# alto-ethernet.net
KiCad netlist of a schematic drawn in EAGLE
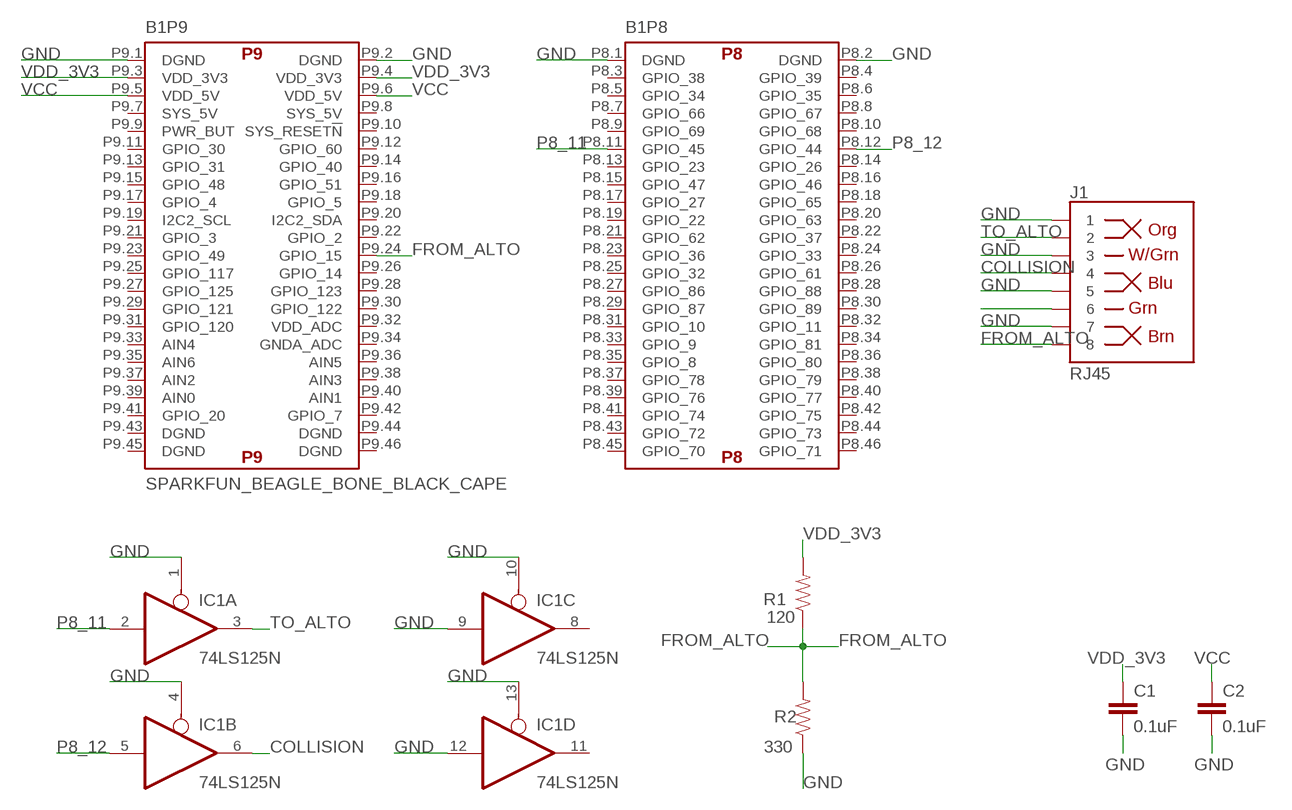
[diagram p0: schematic, sheet 1]

(export (version "E")
  (design (tool "Eeschema 10.0.6"))
  (components
    (comp (ref "B1")
      (value "SPARKFUN_BEAGLE_BONE_BLACK_CAPE")
      (footprint "eagle-import:BEAGLE_BONE_BLACK_CAPE")
      (libsource (lib "eagle-import") (part "SPARKFUN_BEAGLE_BONE_BLACK_CAPE"))
    )
    (comp (ref "C1")
      (value "0.1uF")
      (footprint "eagle-import:CAP-PTH-SMALL-KIT")
      (libsource (lib "eagle-import") (part "0.1UF-KIT-EZ-50V-20%"))
    )
    (comp (ref "C2")
      (value "0.1uF")
      (footprint "eagle-import:CAP-PTH-SMALL-KIT")
      (libsource (lib "eagle-import") (part "0.1UF-KIT-EZ-50V-20%"))
    )
    (comp (ref "IC1")
      (value "74LS125N")
      (footprint "eagle-import:DIL14")
      (libsource (lib "eagle-import") (part "74125NLS"))
    )
    (comp (ref "J1")
      (value "RJ45")
      (footprint "eagle-import:RJ45-8")
      (libsource (lib "eagle-import") (part "RJ45-8"))
    )
    (comp (ref "R1")
      (value "120")
      (footprint "eagle-import:AXIAL-0.3")
      (libsource (lib "eagle-import") (part "RESISTORAXIAL-0.3"))
    )
    (comp (ref "R2")
      (value "330")
      (footprint "eagle-import:AXIAL-0.3")
      (libsource (lib "eagle-import") (part "RESISTORAXIAL-0.3"))
    )
  )
  (nets
    (net (code "1") (name "/COLLISION") (class "Default")
      (node (ref "IC1") (pin "6") (pinfunction "O_6") (pintype "tri_state"))
      (node (ref "J1") (pin "4") (pinfunction "4_4") (pintype "bidirectional"))
    )
    (net (code "2") (name "/FROM_ALTO") (class "Default")
      (node (ref "B1") (pin "P9.24") (pinfunction "GPIO_15_P9.24") (pintype "bidirectional"))
      (node (ref "J1") (pin "8") (pinfunction "8_8") (pintype "bidirectional"))
      (node (ref "R1") (pin "P$1") (pinfunction "1_P$1") (pintype "passive"))
      (node (ref "R2") (pin "P$2") (pinfunction "2_P$2") (pintype "passive"))
    )
    (net (code "3") (name "/GND") (class "Default")
      (node (ref "B1") (pin "P8.1") (pinfunction "DGND_P8.1") (pintype "bidirectional"))
      (node (ref "B1") (pin "P8.2") (pinfunction "DGND_P8.2") (pintype "bidirectional"))
      (node (ref "B1") (pin "P9.1") (pinfunction "DGND_P9.1") (pintype "bidirectional"))
      (node (ref "B1") (pin "P9.2") (pinfunction "DGND_P9.2") (pintype "bidirectional"))
      (node (ref "C1") (pin "2") (pinfunction "2_2") (pintype "passive"))
      (node (ref "C2") (pin "2") (pinfunction "2_2") (pintype "passive"))
      (node (ref "IC1") (pin "1") (pinfunction "OE_1") (pintype "input"))
      (node (ref "IC1") (pin "10") (pinfunction "OE_10") (pintype "input"))
      (node (ref "IC1") (pin "12") (pinfunction "I_12") (pintype "input"))
      (node (ref "IC1") (pin "13") (pinfunction "OE_13") (pintype "input"))
      (node (ref "IC1") (pin "4") (pinfunction "OE_4") (pintype "input"))
      (node (ref "IC1") (pin "9") (pinfunction "I_9") (pintype "input"))
      (node (ref "J1") (pin "1") (pinfunction "1_1") (pintype "bidirectional"))
      (node (ref "J1") (pin "3") (pinfunction "3_3") (pintype "bidirectional"))
      (node (ref "J1") (pin "5") (pinfunction "5_5") (pintype "bidirectional"))
      (node (ref "J1") (pin "7") (pinfunction "7_7") (pintype "bidirectional"))
      (node (ref "R2") (pin "P$1") (pinfunction "1_P$1") (pintype "passive"))
    )
    (net (code "4") (name "/P8_11") (class "Default")
      (node (ref "B1") (pin "P8.11") (pinfunction "GPIO_45_P8.11") (pintype "bidirectional"))
      (node (ref "IC1") (pin "2") (pinfunction "I_2") (pintype "input"))
    )
    (net (code "5") (name "/P8_12") (class "Default")
      (node (ref "B1") (pin "P8.12") (pinfunction "GPIO_44_P8.12") (pintype "bidirectional"))
      (node (ref "IC1") (pin "5") (pinfunction "I_5") (pintype "input"))
    )
    (net (code "6") (name "/TO_ALTO") (class "Default")
      (node (ref "IC1") (pin "3") (pinfunction "O_3") (pintype "tri_state"))
      (node (ref "J1") (pin "2") (pinfunction "2_2") (pintype "bidirectional"))
    )
    (net (code "7") (name "/VCC") (class "Default")
      (node (ref "B1") (pin "P9.5") (pinfunction "VDD_5V_P9.5") (pintype "bidirectional"))
      (node (ref "B1") (pin "P9.6") (pinfunction "VDD_5V_P9.6") (pintype "bidirectional"))
      (node (ref "C2") (pin "1") (pinfunction "1_1") (pintype "passive"))
    )
    (net (code "8") (name "/VDD_3V3") (class "Default")
      (node (ref "B1") (pin "P9.3") (pinfunction "VDD_3V3_P9.3") (pintype "bidirectional"))
      (node (ref "B1") (pin "P9.4") (pinfunction "VDD_3V3_P9.4") (pintype "bidirectional"))
      (node (ref "C1") (pin "1") (pinfunction "1_1") (pintype "passive"))
      (node (ref "R1") (pin "P$2") (pinfunction "2_P$2") (pintype "passive"))
    )
    (net (code "9") (name "unconnected-(B1A-GPIO_8-PadP8.35)") (class "Default")
      (node (ref "B1") (pin "P8.35") (pinfunction "GPIO_8_P8.35") (pintype "bidirectional"))
    )
    (net (code "10") (name "unconnected-(B1A-GPIO_9-PadP8.33)") (class "Default")
      (node (ref "B1") (pin "P8.33") (pinfunction "GPIO_9_P8.33") (pintype "bidirectional"))
    )
    (net (code "11") (name "unconnected-(B1A-GPIO_10-PadP8.31)") (class "Default")
      (node (ref "B1") (pin "P8.31") (pinfunction "GPIO_10_P8.31") (pintype "bidirectional"))
    )
    (net (code "12") (name "unconnected-(B1A-GPIO_11-PadP8.32)") (class "Default")
      (node (ref "B1") (pin "P8.32") (pinfunction "GPIO_11_P8.32") (pintype "bidirectional"))
    )
    (net (code "13") (name "unconnected-(B1A-GPIO_22-PadP8.19)") (class "Default")
      (node (ref "B1") (pin "P8.19") (pinfunction "GPIO_22_P8.19") (pintype "bidirectional"))
    )
    (net (code "14") (name "unconnected-(B1A-GPIO_23-PadP8.13)") (class "Default")
      (node (ref "B1") (pin "P8.13") (pinfunction "GPIO_23_P8.13") (pintype "bidirectional"))
    )
    (net (code "15") (name "unconnected-(B1A-GPIO_26-PadP8.14)") (class "Default")
      (node (ref "B1") (pin "P8.14") (pinfunction "GPIO_26_P8.14") (pintype "bidirectional"))
    )
    (net (code "16") (name "unconnected-(B1A-GPIO_27-PadP8.17)") (class "Default")
      (node (ref "B1") (pin "P8.17") (pinfunction "GPIO_27_P8.17") (pintype "bidirectional"))
    )
    (net (code "17") (name "unconnected-(B1A-GPIO_32-PadP8.25)") (class "Default")
      (node (ref "B1") (pin "P8.25") (pinfunction "GPIO_32_P8.25") (pintype "bidirectional"))
    )
    (net (code "18") (name "unconnected-(B1A-GPIO_33-PadP8.24)") (class "Default")
      (node (ref "B1") (pin "P8.24") (pinfunction "GPIO_33_P8.24") (pintype "bidirectional"))
    )
    (net (code "19") (name "unconnected-(B1A-GPIO_34-PadP8.5)") (class "Default")
      (node (ref "B1") (pin "P8.5") (pinfunction "GPIO_34_P8.5") (pintype "bidirectional"))
    )
    (net (code "20") (name "unconnected-(B1A-GPIO_35-PadP8.6)") (class "Default")
      (node (ref "B1") (pin "P8.6") (pinfunction "GPIO_35_P8.6") (pintype "bidirectional"))
    )
    (net (code "21") (name "unconnected-(B1A-GPIO_36-PadP8.23)") (class "Default")
      (node (ref "B1") (pin "P8.23") (pinfunction "GPIO_36_P8.23") (pintype "bidirectional"))
    )
    (net (code "22") (name "unconnected-(B1A-GPIO_37-PadP8.22)") (class "Default")
      (node (ref "B1") (pin "P8.22") (pinfunction "GPIO_37_P8.22") (pintype "bidirectional"))
    )
    (net (code "23") (name "unconnected-(B1A-GPIO_38-PadP8.3)") (class "Default")
      (node (ref "B1") (pin "P8.3") (pinfunction "GPIO_38_P8.3") (pintype "bidirectional"))
    )
    (net (code "24") (name "unconnected-(B1A-GPIO_39-PadP8.4)") (class "Default")
      (node (ref "B1") (pin "P8.4") (pinfunction "GPIO_39_P8.4") (pintype "bidirectional"))
    )
    (net (code "25") (name "unconnected-(B1A-GPIO_46-PadP8.16)") (class "Default")
      (node (ref "B1") (pin "P8.16") (pinfunction "GPIO_46_P8.16") (pintype "bidirectional"))
    )
    (net (code "26") (name "unconnected-(B1A-GPIO_47-PadP8.15)") (class "Default")
      (node (ref "B1") (pin "P8.15") (pinfunction "GPIO_47_P8.15") (pintype "bidirectional"))
    )
    (net (code "27") (name "unconnected-(B1A-GPIO_61-PadP8.26)") (class "Default")
      (node (ref "B1") (pin "P8.26") (pinfunction "GPIO_61_P8.26") (pintype "bidirectional"))
    )
    (net (code "28") (name "unconnected-(B1A-GPIO_62-PadP8.21)") (class "Default")
      (node (ref "B1") (pin "P8.21") (pinfunction "GPIO_62_P8.21") (pintype "bidirectional"))
    )
    (net (code "29") (name "unconnected-(B1A-GPIO_63-PadP8.20)") (class "Default")
      (node (ref "B1") (pin "P8.20") (pinfunction "GPIO_63_P8.20") (pintype "bidirectional"))
    )
    (net (code "30") (name "unconnected-(B1A-GPIO_65-PadP8.18)") (class "Default")
      (node (ref "B1") (pin "P8.18") (pinfunction "GPIO_65_P8.18") (pintype "bidirectional"))
    )
    (net (code "31") (name "unconnected-(B1A-GPIO_66-PadP8.7)") (class "Default")
      (node (ref "B1") (pin "P8.7") (pinfunction "GPIO_66_P8.7") (pintype "bidirectional"))
    )
    (net (code "32") (name "unconnected-(B1A-GPIO_67-PadP8.8)") (class "Default")
      (node (ref "B1") (pin "P8.8") (pinfunction "GPIO_67_P8.8") (pintype "bidirectional"))
    )
    (net (code "33") (name "unconnected-(B1A-GPIO_68-PadP8.10)") (class "Default")
      (node (ref "B1") (pin "P8.10") (pinfunction "GPIO_68_P8.10") (pintype "bidirectional"))
    )
    (net (code "34") (name "unconnected-(B1A-GPIO_69-PadP8.9)") (class "Default")
      (node (ref "B1") (pin "P8.9") (pinfunction "GPIO_69_P8.9") (pintype "bidirectional"))
    )
    (net (code "35") (name "unconnected-(B1A-GPIO_70-PadP8.45)") (class "Default")
      (node (ref "B1") (pin "P8.45") (pinfunction "GPIO_70_P8.45") (pintype "bidirectional"))
    )
    (net (code "36") (name "unconnected-(B1A-GPIO_71-PadP8.46)") (class "Default")
      (node (ref "B1") (pin "P8.46") (pinfunction "GPIO_71_P8.46") (pintype "bidirectional"))
    )
    (net (code "37") (name "unconnected-(B1A-GPIO_72-PadP8.43)") (class "Default")
      (node (ref "B1") (pin "P8.43") (pinfunction "GPIO_72_P8.43") (pintype "bidirectional"))
    )
    (net (code "38") (name "unconnected-(B1A-GPIO_73-PadP8.44)") (class "Default")
      (node (ref "B1") (pin "P8.44") (pinfunction "GPIO_73_P8.44") (pintype "bidirectional"))
    )
    (net (code "39") (name "unconnected-(B1A-GPIO_74-PadP8.41)") (class "Default")
      (node (ref "B1") (pin "P8.41") (pinfunction "GPIO_74_P8.41") (pintype "bidirectional"))
    )
    (net (code "40") (name "unconnected-(B1A-GPIO_75-PadP8.42)") (class "Default")
      (node (ref "B1") (pin "P8.42") (pinfunction "GPIO_75_P8.42") (pintype "bidirectional"))
    )
    (net (code "41") (name "unconnected-(B1A-GPIO_76-PadP8.39)") (class "Default")
      (node (ref "B1") (pin "P8.39") (pinfunction "GPIO_76_P8.39") (pintype "bidirectional"))
    )
    (net (code "42") (name "unconnected-(B1A-GPIO_77-PadP8.40)") (class "Default")
      (node (ref "B1") (pin "P8.40") (pinfunction "GPIO_77_P8.40") (pintype "bidirectional"))
    )
    (net (code "43") (name "unconnected-(B1A-GPIO_78-PadP8.37)") (class "Default")
      (node (ref "B1") (pin "P8.37") (pinfunction "GPIO_78_P8.37") (pintype "bidirectional"))
    )
    (net (code "44") (name "unconnected-(B1A-GPIO_79-PadP8.38)") (class "Default")
      (node (ref "B1") (pin "P8.38") (pinfunction "GPIO_79_P8.38") (pintype "bidirectional"))
    )
    (net (code "45") (name "unconnected-(B1A-GPIO_80-PadP8.36)") (class "Default")
      (node (ref "B1") (pin "P8.36") (pinfunction "GPIO_80_P8.36") (pintype "bidirectional"))
    )
    (net (code "46") (name "unconnected-(B1A-GPIO_81-PadP8.34)") (class "Default")
      (node (ref "B1") (pin "P8.34") (pinfunction "GPIO_81_P8.34") (pintype "bidirectional"))
    )
    (net (code "47") (name "unconnected-(B1A-GPIO_86-PadP8.27)") (class "Default")
      (node (ref "B1") (pin "P8.27") (pinfunction "GPIO_86_P8.27") (pintype "bidirectional"))
    )
    (net (code "48") (name "unconnected-(B1A-GPIO_87-PadP8.29)") (class "Default")
      (node (ref "B1") (pin "P8.29") (pinfunction "GPIO_87_P8.29") (pintype "bidirectional"))
    )
    (net (code "49") (name "unconnected-(B1A-GPIO_88-PadP8.28)") (class "Default")
      (node (ref "B1") (pin "P8.28") (pinfunction "GPIO_88_P8.28") (pintype "bidirectional"))
    )
    (net (code "50") (name "unconnected-(B1A-GPIO_89-PadP8.30)") (class "Default")
      (node (ref "B1") (pin "P8.30") (pinfunction "GPIO_89_P8.30") (pintype "bidirectional"))
    )
    (net (code "51") (name "unconnected-(B1B-AIN0-PadP9.39)") (class "Default")
      (node (ref "B1") (pin "P9.39") (pinfunction "AIN0_P9.39") (pintype "bidirectional"))
    )
    (net (code "52") (name "unconnected-(B1B-AIN1-PadP9.40)") (class "Default")
      (node (ref "B1") (pin "P9.40") (pinfunction "AIN1_P9.40") (pintype "bidirectional"))
    )
    (net (code "53") (name "unconnected-(B1B-AIN2-PadP9.37)") (class "Default")
      (node (ref "B1") (pin "P9.37") (pinfunction "AIN2_P9.37") (pintype "bidirectional"))
    )
    (net (code "54") (name "unconnected-(B1B-AIN3-PadP9.38)") (class "Default")
      (node (ref "B1") (pin "P9.38") (pinfunction "AIN3_P9.38") (pintype "bidirectional"))
    )
    (net (code "55") (name "unconnected-(B1B-AIN4-PadP9.33)") (class "Default")
      (node (ref "B1") (pin "P9.33") (pinfunction "AIN4_P9.33") (pintype "bidirectional"))
    )
    (net (code "56") (name "unconnected-(B1B-AIN5-PadP9.36)") (class "Default")
      (node (ref "B1") (pin "P9.36") (pinfunction "AIN5_P9.36") (pintype "bidirectional"))
    )
    (net (code "57") (name "unconnected-(B1B-AIN6-PadP9.35)") (class "Default")
      (node (ref "B1") (pin "P9.35") (pinfunction "AIN6_P9.35") (pintype "bidirectional"))
    )
    (net (code "58") (name "unconnected-(B1B-DGND-PadP9.43)") (class "Default")
      (node (ref "B1") (pin "P9.43") (pinfunction "DGND_P9.43") (pintype "bidirectional"))
    )
    (net (code "59") (name "unconnected-(B1B-DGND-PadP9.44)") (class "Default")
      (node (ref "B1") (pin "P9.44") (pinfunction "DGND_P9.44") (pintype "bidirectional"))
    )
    (net (code "60") (name "unconnected-(B1B-DGND-PadP9.45)") (class "Default")
      (node (ref "B1") (pin "P9.45") (pinfunction "DGND_P9.45") (pintype "bidirectional"))
    )
    (net (code "61") (name "unconnected-(B1B-DGND-PadP9.46)") (class "Default")
      (node (ref "B1") (pin "P9.46") (pinfunction "DGND_P9.46") (pintype "bidirectional"))
    )
    (net (code "62") (name "unconnected-(B1B-GNDA_ADC-PadP9.34)") (class "Default")
      (node (ref "B1") (pin "P9.34") (pinfunction "GNDA_ADC_P9.34") (pintype "bidirectional"))
    )
    (net (code "63") (name "unconnected-(B1B-GPIO_2-PadP9.22)") (class "Default")
      (node (ref "B1") (pin "P9.22") (pinfunction "GPIO_2_P9.22") (pintype "bidirectional"))
    )
    (net (code "64") (name "unconnected-(B1B-GPIO_3-PadP9.21)") (class "Default")
      (node (ref "B1") (pin "P9.21") (pinfunction "GPIO_3_P9.21") (pintype "bidirectional"))
    )
    (net (code "65") (name "unconnected-(B1B-GPIO_4-PadP9.17)") (class "Default")
      (node (ref "B1") (pin "P9.17") (pinfunction "GPIO_4_P9.17") (pintype "bidirectional"))
    )
    (net (code "66") (name "unconnected-(B1B-GPIO_5-PadP9.18)") (class "Default")
      (node (ref "B1") (pin "P9.18") (pinfunction "GPIO_5_P9.18") (pintype "bidirectional"))
    )
    (net (code "67") (name "unconnected-(B1B-GPIO_7-PadP9.42)") (class "Default")
      (node (ref "B1") (pin "P9.42") (pinfunction "GPIO_7_P9.42") (pintype "bidirectional"))
    )
    (net (code "68") (name "unconnected-(B1B-GPIO_14-PadP9.26)") (class "Default")
      (node (ref "B1") (pin "P9.26") (pinfunction "GPIO_14_P9.26") (pintype "bidirectional"))
    )
    (net (code "69") (name "unconnected-(B1B-GPIO_20-PadP9.41)") (class "Default")
      (node (ref "B1") (pin "P9.41") (pinfunction "GPIO_20_P9.41") (pintype "bidirectional"))
    )
    (net (code "70") (name "unconnected-(B1B-GPIO_30-PadP9.11)") (class "Default")
      (node (ref "B1") (pin "P9.11") (pinfunction "GPIO_30_P9.11") (pintype "bidirectional"))
    )
    (net (code "71") (name "unconnected-(B1B-GPIO_31-PadP9.13)") (class "Default")
      (node (ref "B1") (pin "P9.13") (pinfunction "GPIO_31_P9.13") (pintype "bidirectional"))
    )
    (net (code "72") (name "unconnected-(B1B-GPIO_40-PadP9.14)") (class "Default")
      (node (ref "B1") (pin "P9.14") (pinfunction "GPIO_40_P9.14") (pintype "bidirectional"))
    )
    (net (code "73") (name "unconnected-(B1B-GPIO_48-PadP9.15)") (class "Default")
      (node (ref "B1") (pin "P9.15") (pinfunction "GPIO_48_P9.15") (pintype "bidirectional"))
    )
    (net (code "74") (name "unconnected-(B1B-GPIO_49-PadP9.23)") (class "Default")
      (node (ref "B1") (pin "P9.23") (pinfunction "GPIO_49_P9.23") (pintype "bidirectional"))
    )
    (net (code "75") (name "unconnected-(B1B-GPIO_51-PadP9.16)") (class "Default")
      (node (ref "B1") (pin "P9.16") (pinfunction "GPIO_51_P9.16") (pintype "bidirectional"))
    )
    (net (code "76") (name "unconnected-(B1B-GPIO_60-PadP9.12)") (class "Default")
      (node (ref "B1") (pin "P9.12") (pinfunction "GPIO_60_P9.12") (pintype "bidirectional"))
    )
    (net (code "77") (name "unconnected-(B1B-GPIO_117-PadP9.25)") (class "Default")
      (node (ref "B1") (pin "P9.25") (pinfunction "GPIO_117_P9.25") (pintype "bidirectional"))
    )
    (net (code "78") (name "unconnected-(B1B-GPIO_120-PadP9.31)") (class "Default")
      (node (ref "B1") (pin "P9.31") (pinfunction "GPIO_120_P9.31") (pintype "bidirectional"))
    )
    (net (code "79") (name "unconnected-(B1B-GPIO_121-PadP9.29)") (class "Default")
      (node (ref "B1") (pin "P9.29") (pinfunction "GPIO_121_P9.29") (pintype "bidirectional"))
    )
    (net (code "80") (name "unconnected-(B1B-GPIO_122-PadP9.30)") (class "Default")
      (node (ref "B1") (pin "P9.30") (pinfunction "GPIO_122_P9.30") (pintype "bidirectional"))
    )
    (net (code "81") (name "unconnected-(B1B-GPIO_123-PadP9.28)") (class "Default")
      (node (ref "B1") (pin "P9.28") (pinfunction "GPIO_123_P9.28") (pintype "bidirectional"))
    )
    (net (code "82") (name "unconnected-(B1B-GPIO_125-PadP9.27)") (class "Default")
      (node (ref "B1") (pin "P9.27") (pinfunction "GPIO_125_P9.27") (pintype "bidirectional"))
    )
    (net (code "83") (name "unconnected-(B1B-I2C2_SCL-PadP9.19)") (class "Default")
      (node (ref "B1") (pin "P9.19") (pinfunction "I2C2_SCL_P9.19") (pintype "bidirectional"))
    )
    (net (code "84") (name "unconnected-(B1B-I2C2_SDA-PadP9.20)") (class "Default")
      (node (ref "B1") (pin "P9.20") (pinfunction "I2C2_SDA_P9.20") (pintype "bidirectional"))
    )
    (net (code "85") (name "unconnected-(B1B-PWR_BUT-PadP9.9)") (class "Default")
      (node (ref "B1") (pin "P9.9") (pinfunction "PWR_BUT_P9.9") (pintype "bidirectional"))
    )
    (net (code "86") (name "unconnected-(B1B-SYS_5V-PadP9.7)") (class "Default")
      (node (ref "B1") (pin "P9.7") (pinfunction "SYS_5V_P9.7") (pintype "bidirectional"))
    )
    (net (code "87") (name "unconnected-(B1B-SYS_5V-PadP9.8)") (class "Default")
      (node (ref "B1") (pin "P9.8") (pinfunction "SYS_5V_P9.8") (pintype "bidirectional"))
    )
    (net (code "88") (name "unconnected-(B1B-SYS_RESET~{N}-PadP9.10)") (class "Default")
      (node (ref "B1") (pin "P9.10") (pinfunction "SYS_RESET~{N}_P9.10") (pintype "bidirectional"))
    )
    (net (code "89") (name "unconnected-(B1B-VDD_ADC-PadP9.32)") (class "Default")
      (node (ref "B1") (pin "P9.32") (pinfunction "VDD_ADC_P9.32") (pintype "bidirectional"))
    )
    (net (code "90") (name "unconnected-(IC1C-O-Pad8)") (class "Default")
      (node (ref "IC1") (pin "8") (pinfunction "O_8") (pintype "tri_state"))
    )
    (net (code "91") (name "unconnected-(IC1D-O-Pad11)") (class "Default")
      (node (ref "IC1") (pin "11") (pinfunction "O_11") (pintype "tri_state"))
    )
    (net (code "92") (name "unconnected-(J1-Pad6)") (class "Default")
      (node (ref "J1") (pin "6") (pinfunction "6_6") (pintype "bidirectional"))
    )
  )
)
